# STB_Sensors.net
KiCad netlist of a schematic drawn in Altium Designer
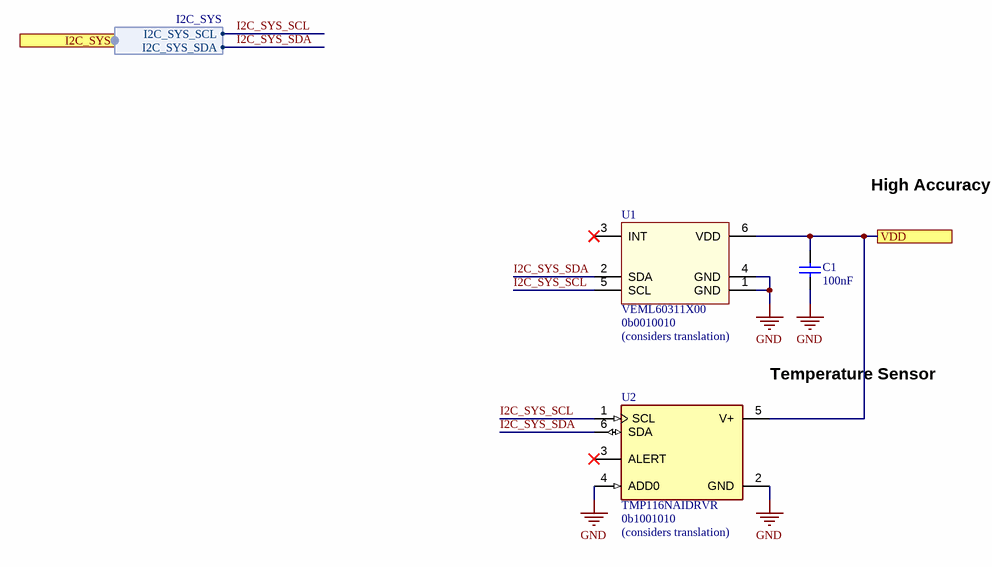
[diagram p0: STB_Sensors.SchDoc]

(export (version "E")
  (design (tool "Eeschema 10.0.6"))
  (components
    (comp (ref "C1")
      (value "100nF")
      (footprint "CAPC1050X55X23LL05T13")
      (description "Chip Capacitor, 100 nF, +/- 10%, 16 V, -55 to 125 degC, 0402 (1005 Metric), RoHS, Tape and Reel")
      (fields
        (field (name "MANUFACTURER") "Samsung Electro-Mechanics")
        (field (name "MANUFACTURER PART NUMBER") "CL05B104KO5NNNC")
      )
      (libsource (lib "Altium Content Vault") (part "CAP-NP-2"))
    )
    (comp (ref "U1")
      (value "VEML60311X00")
      (footprint "6-SMD - No Thermal Pad_2")
      (description "Ambient Light Sensor, I²C 6-SMD, No Lead")
      (fields
        (field (name "MFR") "Vishay Semiconductor Opto Division")
        (field (name "MANUFACTURER") "Vishay")
      )
      (libsource (lib "ETHZ Vault") (part "VEML60311X00"))
    )
    (comp (ref "U2")
      (value "TMP116NAIDRVR")
      (footprint "FP-DRV0006B-MFG")
      (description "SENSOR DIGITAL -55C-125C 6WSON")
      (fields
        (field (name "MANUFACTURER") "Texas Instruments")
        (field (name "OCTOPART") "https://octopart.com/tmp116naidrvr-texas+instruments-82367758")
        (field (name "ADDRESS") "0b1001010")
      )
      (libsource (lib "Altium Content Vault") (part "662a3f5fc0b2df02352a1f1bb70b9b8"))
    )
  )
  (nets
    (net (code "2") (name "/I2C_SYS_SCL") (class "Default")
      (node (ref "U1") (pin "5") (pinfunction "SCL_5") (pintype "passive"))
      (node (ref "U2") (pin "1") (pinfunction "SCL_1") (pintype "input"))
    )
    (net (code "3") (name "/I2C_SYS_SDA") (class "Default")
      (node (ref "U1") (pin "2") (pinfunction "SDA_2") (pintype "passive"))
      (node (ref "U2") (pin "6") (pinfunction "SDA_6") (pintype "bidirectional"))
    )
    (net (code "4") (name "/VDD") (class "Default")
      (node (ref "C1") (pin "2") (pinfunction "2_2") (pintype "passive"))
      (node (ref "U1") (pin "6") (pinfunction "VDD_6") (pintype "passive"))
      (node (ref "U2") (pin "5") (pinfunction "V+_5") (pintype "power_in"))
    )
    (net (code "6") (name "GND") (class "Default")
      (node (ref "C1") (pin "1") (pinfunction "1_1") (pintype "passive"))
      (node (ref "U1") (pin "1") (pinfunction "GND_1") (pintype "passive"))
      (node (ref "U1") (pin "4") (pinfunction "GND_4") (pintype "passive"))
      (node (ref "U2") (pin "2") (pinfunction "GND_2") (pintype "power_in"))
      (node (ref "U2") (pin "4") (pinfunction "ADD0_4") (pintype "input"))
    )
    (net (code "7") (name "unconnected-(U1-INT-Pad3)") (class "Default")
      (node (ref "U1") (pin "3") (pinfunction "INT_3") (pintype "passive+no_connect"))
    )
    (net (code "8") (name "unconnected-(U2-ALERT-Pad3)") (class "Default")
      (node (ref "U2") (pin "3") (pinfunction "ALERT_3") (pintype "open_collector+no_connect"))
    )
  )
)
